# IO2.net
KiCad netlist of a schematic drawn in Altium Designer
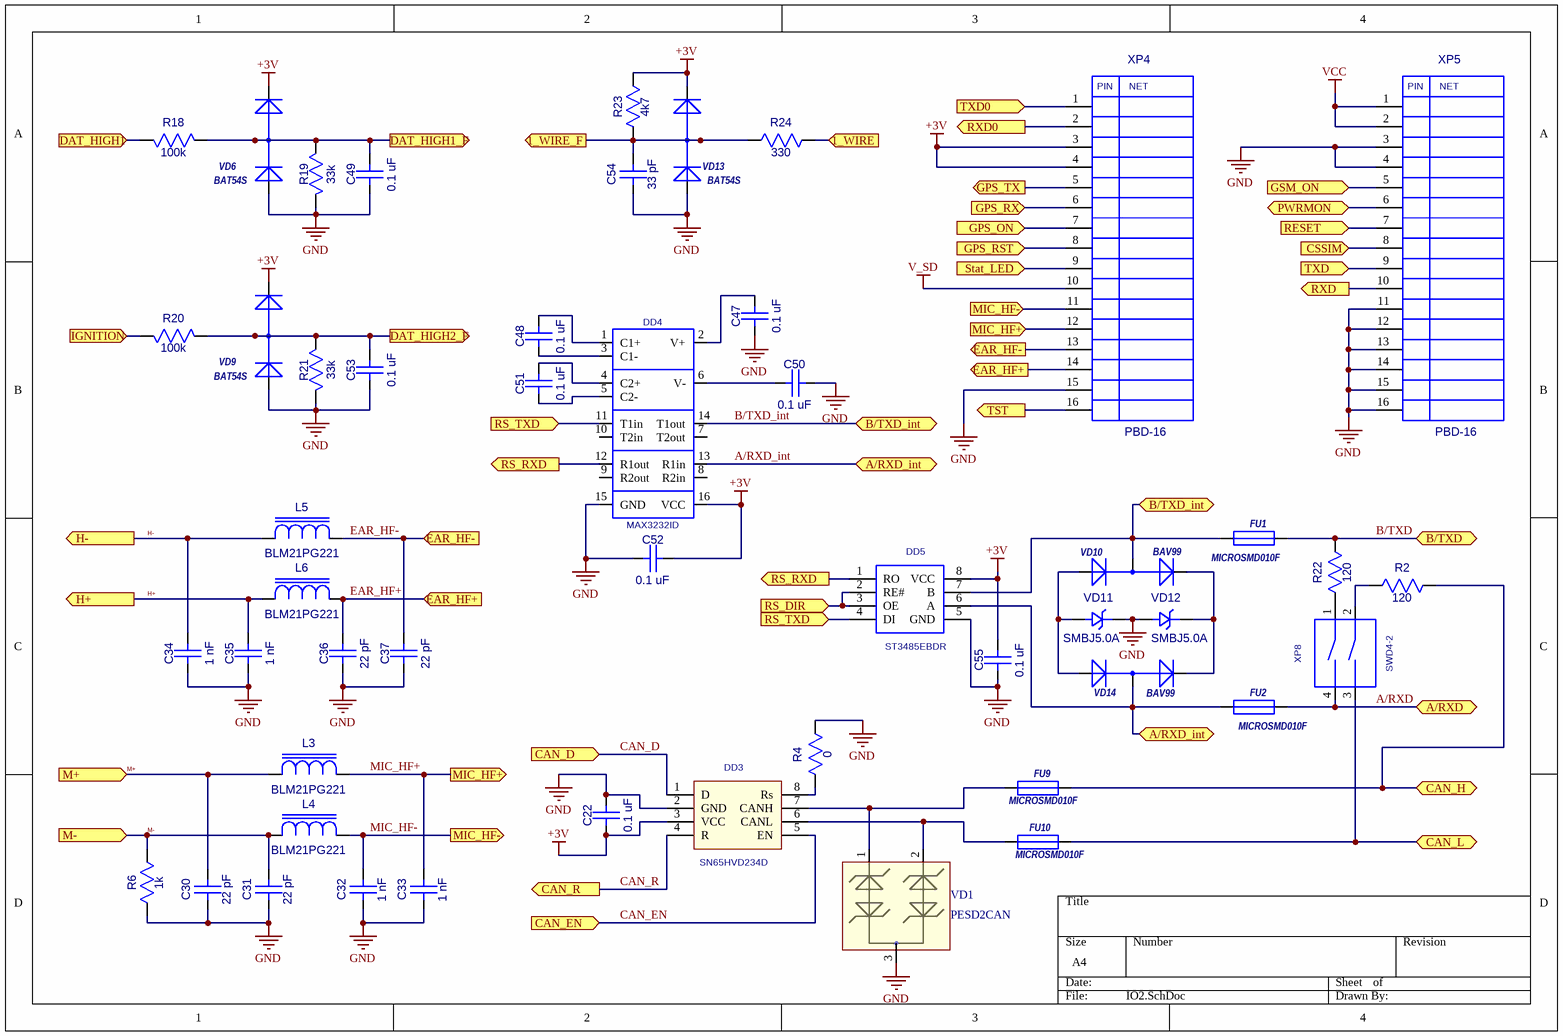
[diagram p0: IO2.SchDoc]

(export (version "E")
  (design (tool "Eeschema 10.0.6"))
  (components
    (comp (ref "C22")
      (value "0.1 uF")
      (footprint "CC0603-3M")
      (description "CC0603")
      (libsource (lib "*") (part "CC0603"))
    )
    (comp (ref "C30")
      (value "22 pF")
      (footprint "CC0603-3M")
      (description "CC0603")
      (libsource (lib "*") (part "CC0603"))
    )
    (comp (ref "C31")
      (value "22 pF")
      (footprint "CC0603-3M")
      (description "CC0603")
      (libsource (lib "*") (part "CC0603"))
    )
    (comp (ref "C32")
      (value "1 nF")
      (footprint "CC0603-3M")
      (description "CC0603")
      (libsource (lib "*") (part "CC0603"))
    )
    (comp (ref "C33")
      (value "1 nF")
      (footprint "CC0603-3M")
      (description "CC0603")
      (libsource (lib "*") (part "CC0603"))
    )
    (comp (ref "C34")
      (value "1 nF")
      (footprint "CC0603-3M")
      (description "CC0603")
      (libsource (lib "*") (part "CC0603"))
    )
    (comp (ref "C35")
      (value "1 nF")
      (footprint "CC0603-3M")
      (description "CC0603")
      (libsource (lib "*") (part "CC0603"))
    )
    (comp (ref "C36")
      (value "22 pF")
      (footprint "CC0603-3M")
      (description "CC0603")
      (libsource (lib "*") (part "CC0603"))
    )
    (comp (ref "C37")
      (value "22 pF")
      (footprint "CC0603-3M")
      (description "CC0603")
      (libsource (lib "*") (part "CC0603"))
    )
    (comp (ref "C47")
      (value "0.1 uF")
      (footprint "CC0603-3M")
      (description "CC0603")
      (libsource (lib "*") (part "CC0603"))
    )
    (comp (ref "C48")
      (value "0.1 uF")
      (footprint "CC0603-3M")
      (description "CC0603")
      (libsource (lib "*") (part "CC0603"))
    )
    (comp (ref "C49")
      (value "0.1 uF")
      (footprint "CC0603-3M")
      (description "CC0603")
      (libsource (lib "*") (part "CC0603"))
    )
    (comp (ref "C50")
      (value "0.1 uF")
      (footprint "CC0603-3M")
      (description "CC0603")
      (libsource (lib "*") (part "CC0603"))
    )
    (comp (ref "C51")
      (value "0.1 uF")
      (footprint "CC0603-3M")
      (description "CC0603")
      (libsource (lib "*") (part "CC0603"))
    )
    (comp (ref "C52")
      (value "0.1 uF")
      (footprint "CC0603-3M")
      (description "CC0603")
      (libsource (lib "*") (part "CC0603"))
    )
    (comp (ref "C53")
      (value "0.1 uF")
      (footprint "CC0603-3M")
      (description "CC0603")
      (libsource (lib "*") (part "CC0603"))
    )
    (comp (ref "C54")
      (value "33 pF")
      (footprint "CC0603-3M")
      (description "CC0603")
      (libsource (lib "*") (part "CC0603"))
    )
    (comp (ref "C55")
      (value "0.1 uF")
      (footprint "CC0603-3M")
      (description "CC0603")
      (libsource (lib "*") (part "CC0603"))
    )
    (comp (ref "DD3")
      (value "SN65HVD234D")
      (footprint "SO-8")
      (description "CAN Transceiver")
      (libsource (lib "gprs_modem") (part "SN65HVD234D"))
    )
    (comp (ref "DD4")
      (value "MAX3232ID")
      (footprint "SO16_M")
      (description "ST232BD/CD")
      (libsource (lib "Schetchik") (part "ST232BD/CD"))
    )
    (comp (ref "DD5")
      (value "ST3485EBDR")
      (footprint "SO-8")
      (description "SP485")
      (libsource (lib "Schetchik") (part "SP485"))
    )
    (comp (ref "FU1")
      (value "MICROSMD010F")
      (footprint "RC1210")
      (description "MICROSMD")
      (libsource (lib "*") (part "MICROSMD"))
    )
    (comp (ref "FU2")
      (value "MICROSMD010F")
      (footprint "RC1210")
      (description "MICROSMD")
      (libsource (lib "*") (part "MICROSMD"))
    )
    (comp (ref "FU9")
      (value "MICROSMD010F")
      (footprint "RC1210")
      (description "MICROSMD")
      (libsource (lib "*") (part "MICROSMD"))
    )
    (comp (ref "FU10")
      (value "MICROSMD010F")
      (footprint "RC1210")
      (description "MICROSMD")
      (libsource (lib "*") (part "MICROSMD"))
    )
    (comp (ref "L3")
      (value "BLM21PG221")
      (footprint "RC0805-MIDI-2")
      (libsource (lib "") (part "BLM21PG221_1"))
    )
    (comp (ref "L4")
      (value "BLM21PG221")
      (footprint "RC0805-MIDI-2")
      (libsource (lib "") (part "BLM21PG221_1"))
    )
    (comp (ref "L5")
      (value "BLM21PG221")
      (footprint "RC0805-MIDI-2")
      (libsource (lib "*") (part "BLM21PG221"))
    )
    (comp (ref "L6")
      (value "BLM21PG221")
      (footprint "RC0805-MIDI-2")
      (libsource (lib "*") (part "BLM21PG221"))
    )
    (comp (ref "R2")
      (value "120")
      (footprint "RC0805_IPC_NOM")
      (description "RC0805")
      (libsource (lib "gprs_modem") (part "RC0805"))
    )
    (comp (ref "R4")
      (value "0")
      (footprint "RC0603-3M")
      (description "RC0603")
      (libsource (lib "*") (part "RC0603"))
    )
    (comp (ref "R6")
      (value "1k")
      (footprint "RC0603-3M")
      (description "RC0603")
      (libsource (lib "*") (part "RC0603"))
    )
    (comp (ref "R18")
      (value "100k")
      (footprint "RC0603-3M")
      (description "RC0603")
      (libsource (lib "*") (part "RC0603"))
    )
    (comp (ref "R19")
      (value "33k")
      (footprint "RC0603-3M")
      (description "RC0603")
      (libsource (lib "*") (part "RC0603"))
    )
    (comp (ref "R20")
      (value "100k")
      (footprint "RC0603-3M")
      (description "RC0603")
      (libsource (lib "*") (part "RC0603"))
    )
    (comp (ref "R21")
      (value "33k")
      (footprint "RC0603-3M")
      (description "RC0603")
      (libsource (lib "*") (part "RC0603"))
    )
    (comp (ref "R22")
      (value "120")
      (footprint "RC0805_IPC_NOM")
      (description "RC0805")
      (libsource (lib "gprs_modem") (part "RC0805"))
    )
    (comp (ref "R23")
      (value "4k7")
      (footprint "RC0603-3M")
      (description "RC0603")
      (libsource (lib "*") (part "RC0603"))
    )
    (comp (ref "R24")
      (value "330")
      (footprint "RC0603-3M")
      (description "RC0603")
      (libsource (lib "*") (part "RC0603"))
    )
    (comp (ref "VD1")
      (value "PESD2CAN")
      (footprint "SOT-23(123)")
      (description "TVS for CAN")
      (libsource (lib "gprs_modem") (part "PESD2CAN"))
    )
    (comp (ref "VD6") (value "BAT54S") (footprint "SOT-23(GSD)") (libsource (lib "*") (part "BAT54S")))
    (comp (ref "VD9") (value "BAT54S") (footprint "SOT-23(GSD)") (libsource (lib "*") (part "BAT54S")))
    (comp (ref "VD10")
      (value "BAV99")
      (footprint "SOT-23(GSD)")
      (description "1.0 Ampere General Purpose Rectifier")
      (libsource (lib "gprs_modem") (part "BAV99"))
    )
    (comp (ref "VD11")
      (value "SMBJ5.0A")
      (footprint "SMB")
      (description "SMBJ")
      (libsource (lib "gprs_modem") (part "SMBJ"))
    )
    (comp (ref "VD12")
      (value "SMBJ5.0A")
      (footprint "SMB")
      (description "SMBJ")
      (libsource (lib "gprs_modem") (part "SMBJ"))
    )
    (comp (ref "VD13")
      (value "BAT54S")
      (footprint "SOT-23(GSD)")
      (description "1.0 Ampere General Purpose Rectifier")
      (libsource (lib "gprs_modem") (part "BAT54S"))
    )
    (comp (ref "VD14")
      (value "BAV99")
      (footprint "SOT-23(GSD)")
      (description "1.0 Ampere General Purpose Rectifier")
      (libsource (lib "gprs_modem") (part "BAV99"))
    )
    (comp (ref "XP4") (value "PBD-16") (footprint "PBD16") (libsource (lib "gprs_modem") (part "PBD-16")))
    (comp (ref "XP5") (value "PBD-16") (footprint "PBD16") (libsource (lib "gprs_modem") (part "PBD-16")))
    (comp (ref "XP8") (value "SWD4-2") (footprint "SWD4-2") (libsource (lib "gprs_modem") (part "SWD4-2")))
  )
  (nets
    (net (code "1") (name "+3V") (class "Default")
      (node (ref "C22") (pin "1") (pinfunction "A_1") (pintype "passive"))
      (node (ref "C52") (pin "2") (pinfunction "B_2") (pintype "passive"))
      (node (ref "C55") (pin "2") (pinfunction "B_2") (pintype "passive"))
      (node (ref "DD3") (pin "3") (pinfunction "VCC_3") (pintype "passive"))
      (node (ref "DD4") (pin "16") (pinfunction "VCC_16") (pintype "passive"))
      (node (ref "DD5") (pin "8") (pinfunction "VCC_8") (pintype "passive"))
      (node (ref "R23") (pin "1") (pinfunction "A_1") (pintype "passive"))
      (node (ref "VD13") (pin "2") (pinfunction "K_2") (pintype "passive"))
      (node (ref "VD6") (pin "2") (pinfunction "K_2") (pintype "passive"))
      (node (ref "VD9") (pin "2") (pinfunction "K_2") (pintype "passive"))
      (node (ref "XP4") (pin "3") (pinfunction "3_3") (pintype "passive"))
      (node (ref "XP4") (pin "4") (pinfunction "4_4") (pintype "passive"))
    )
    (net (code "2") (name "/1_WIRE") (class "Default")
      (node (ref "R24") (pin "2") (pinfunction "B_2") (pintype "passive"))
    )
    (net (code "3") (name "/1_WIRE_F") (class "Default")
      (node (ref "C54") (pin "2") (pinfunction "B_2") (pintype "passive"))
      (node (ref "R23") (pin "2") (pinfunction "B_2") (pintype "passive"))
      (node (ref "R24") (pin "1") (pinfunction "A_1") (pintype "passive"))
      (node (ref "VD13") (pin "3") (pinfunction "AK_3") (pintype "passive"))
    )
    (net (code "4") (name "/A{slash}RXD") (class "Default")
      (node (ref "FU2") (pin "1") (pintype "passive"))
      (node (ref "XP8") (pin "4") (pintype "passive"))
    )
    (net (code "5") (name "/A{slash}RXD_int") (class "Default")
      (node (ref "DD4") (pin "13") (pinfunction "R1in_13") (pintype "passive"))
      (node (ref "DD5") (pin "6") (pinfunction "A_6") (pintype "passive"))
      (node (ref "FU2") (pin "2") (pintype "passive"))
      (node (ref "VD14") (pin "3") (pinfunction "AK_3") (pintype "passive"))
    )
    (net (code "6") (name "/B{slash}TXD") (class "Default")
      (node (ref "FU1") (pin "1") (pintype "passive"))
      (node (ref "R22") (pin "2") (pinfunction "B_2") (pintype "passive"))
    )
    (net (code "7") (name "/B{slash}TXD_int") (class "Default")
      (node (ref "DD4") (pin "14") (pinfunction "T1out_14") (pintype "passive"))
      (node (ref "DD5") (pin "7") (pinfunction "B_7") (pintype "passive"))
      (node (ref "FU1") (pin "2") (pintype "passive"))
      (node (ref "VD10") (pin "3") (pinfunction "AK_3") (pintype "passive"))
    )
    (net (code "8") (name "/CAN_D") (class "Default")
      (node (ref "DD3") (pin "1") (pinfunction "D_1") (pintype "passive"))
    )
    (net (code "9") (name "/CAN_EN") (class "Default")
      (node (ref "DD3") (pin "5") (pinfunction "EN_5") (pintype "passive"))
    )
    (net (code "10") (name "/CAN_H") (class "Default")
      (node (ref "FU9") (pin "1") (pintype "passive"))
      (node (ref "R2") (pin "2") (pinfunction "B_2") (pintype "passive"))
    )
    (net (code "11") (name "/CAN_L") (class "Default")
      (node (ref "FU10") (pin "1") (pintype "passive"))
      (node (ref "XP8") (pin "3") (pintype "passive"))
    )
    (net (code "12") (name "/CAN_R") (class "Default")
      (node (ref "DD3") (pin "4") (pinfunction "R_4") (pintype "passive"))
    )
    (net (code "13") (name "/CSSIM") (class "Default")
      (node (ref "XP5") (pin "8") (pinfunction "8_8") (pintype "passive"))
    )
    (net (code "14") (name "/DAT_HIGH1") (class "Default")
      (node (ref "R18") (pin "2") (pinfunction "B_2") (pintype "passive"))
    )
    (net (code "15") (name "/DAT_HIGH1_F") (class "Default")
      (node (ref "C49") (pin "2") (pinfunction "B_2") (pintype "passive"))
      (node (ref "R18") (pin "1") (pinfunction "A_1") (pintype "passive"))
      (node (ref "R19") (pin "1") (pinfunction "A_1") (pintype "passive"))
      (node (ref "VD6") (pin "3") (pinfunction "AK_3") (pintype "passive"))
    )
    (net (code "16") (name "/DAT_HIGH2_F") (class "Default")
      (node (ref "C53") (pin "2") (pinfunction "B_2") (pintype "passive"))
      (node (ref "R20") (pin "1") (pinfunction "A_1") (pintype "passive"))
      (node (ref "R21") (pin "1") (pinfunction "A_1") (pintype "passive"))
      (node (ref "VD9") (pin "3") (pinfunction "AK_3") (pintype "passive"))
    )
    (net (code "17") (name "/EAR_HF+") (class "Default")
      (node (ref "C36") (pin "2") (pinfunction "B_2") (pintype "passive"))
      (node (ref "L6") (pin "1") (pinfunction "A_1") (pintype "passive"))
      (node (ref "XP4") (pin "14") (pinfunction "14_14") (pintype "passive"))
    )
    (net (code "18") (name "/EAR_HF-") (class "Default")
      (node (ref "C37") (pin "2") (pinfunction "B_2") (pintype "passive"))
      (node (ref "L5") (pin "1") (pinfunction "A_1") (pintype "passive"))
      (node (ref "XP4") (pin "13") (pinfunction "13_13") (pintype "passive"))
    )
    (net (code "19") (name "/GPS_ON") (class "Default")
      (node (ref "XP4") (pin "7") (pinfunction "7_7") (pintype "passive"))
    )
    (net (code "20") (name "/GPS_RST") (class "Default")
      (node (ref "XP4") (pin "8") (pinfunction "8_8") (pintype "passive"))
    )
    (net (code "21") (name "/GPS_RX") (class "Default")
      (node (ref "XP4") (pin "6") (pinfunction "6_6") (pintype "passive"))
    )
    (net (code "22") (name "/GPS_TX") (class "Default")
      (node (ref "XP4") (pin "5") (pinfunction "5_5") (pintype "passive"))
    )
    (net (code "23") (name "/GSM_ON") (class "Default")
      (node (ref "XP5") (pin "5") (pinfunction "5_5") (pintype "passive"))
    )
    (net (code "24") (name "/H+") (class "Default")
      (node (ref "C35") (pin "2") (pinfunction "B_2") (pintype "passive"))
      (node (ref "L6") (pin "2") (pinfunction "B_2") (pintype "passive"))
    )
    (net (code "25") (name "/H-") (class "Default")
      (node (ref "C34") (pin "2") (pinfunction "B_2") (pintype "passive"))
      (node (ref "L5") (pin "2") (pinfunction "B_2") (pintype "passive"))
    )
    (net (code "26") (name "/IGNITION") (class "Default")
      (node (ref "R20") (pin "2") (pinfunction "B_2") (pintype "passive"))
    )
    (net (code "27") (name "/M+") (class "Default")
      (node (ref "C30") (pin "2") (pinfunction "B_2") (pintype "passive"))
      (node (ref "L3") (pin "1") (pinfunction "A_1") (pintype "passive"))
    )
    (net (code "28") (name "/M-") (class "Default")
      (node (ref "C31") (pin "2") (pinfunction "B_2") (pintype "passive"))
      (node (ref "L4") (pin "1") (pinfunction "A_1") (pintype "passive"))
      (node (ref "R6") (pin "2") (pinfunction "B_2") (pintype "passive"))
    )
    (net (code "29") (name "/MIC_HF+") (class "Default")
      (node (ref "C33") (pin "2") (pinfunction "B_2") (pintype "passive"))
      (node (ref "L3") (pin "2") (pinfunction "B_2") (pintype "passive"))
      (node (ref "XP4") (pin "12") (pinfunction "12_12") (pintype "passive"))
    )
    (net (code "30") (name "/MIC_HF-") (class "Default")
      (node (ref "C32") (pin "2") (pinfunction "B_2") (pintype "passive"))
      (node (ref "L4") (pin "2") (pinfunction "B_2") (pintype "passive"))
      (node (ref "XP4") (pin "11") (pinfunction "11_11") (pintype "passive"))
    )
    (net (code "31") (name "/PWRMON") (class "Default")
      (node (ref "XP5") (pin "6") (pinfunction "6_6") (pintype "passive"))
    )
    (net (code "32") (name "/RESET") (class "Default")
      (node (ref "XP5") (pin "7") (pinfunction "7_7") (pintype "passive"))
    )
    (net (code "33") (name "/RS_DIR") (class "Default")
      (node (ref "DD5") (pin "2") (pinfunction "RE#_2") (pintype "passive"))
      (node (ref "DD5") (pin "3") (pinfunction "OE_3") (pintype "passive"))
    )
    (net (code "34") (name "/RS_RXD") (class "Default")
      (node (ref "DD4") (pin "12") (pinfunction "R1out_12") (pintype "passive"))
      (node (ref "DD5") (pin "1") (pinfunction "RO_1") (pintype "passive"))
    )
    (net (code "35") (name "/RS_TXD") (class "Default")
      (node (ref "DD4") (pin "11") (pinfunction "T1in_11") (pintype "passive"))
      (node (ref "DD5") (pin "4") (pinfunction "DI_4") (pintype "passive"))
    )
    (net (code "36") (name "/RXD") (class "Default")
      (node (ref "XP5") (pin "10") (pinfunction "10_10") (pintype "passive"))
    )
    (net (code "37") (name "/RXD0") (class "Default")
      (node (ref "XP4") (pin "2") (pinfunction "2_2") (pintype "passive"))
    )
    (net (code "38") (name "/Stat_LED") (class "Default")
      (node (ref "XP4") (pin "9") (pinfunction "9_9") (pintype "passive"))
    )
    (net (code "39") (name "/TST") (class "Default")
      (node (ref "XP4") (pin "16") (pinfunction "16_16") (pintype "passive"))
    )
    (net (code "40") (name "/TXD") (class "Default")
      (node (ref "XP5") (pin "9") (pinfunction "9_9") (pintype "passive"))
    )
    (net (code "41") (name "/TXD0") (class "Default")
      (node (ref "XP4") (pin "1") (pinfunction "1_1") (pintype "passive"))
    )
    (net (code "42") (name "GND") (class "Default")
      (node (ref "C22") (pin "2") (pinfunction "B_2") (pintype "passive"))
      (node (ref "C30") (pin "1") (pinfunction "A_1") (pintype "passive"))
      (node (ref "C31") (pin "1") (pinfunction "A_1") (pintype "passive"))
      (node (ref "C32") (pin "1") (pinfunction "A_1") (pintype "passive"))
      (node (ref "C33") (pin "1") (pinfunction "A_1") (pintype "passive"))
      (node (ref "C34") (pin "1") (pinfunction "A_1") (pintype "passive"))
      (node (ref "C35") (pin "1") (pinfunction "A_1") (pintype "passive"))
      (node (ref "C36") (pin "1") (pinfunction "A_1") (pintype "passive"))
      (node (ref "C37") (pin "1") (pinfunction "A_1") (pintype "passive"))
      (node (ref "C47") (pin "1") (pinfunction "A_1") (pintype "passive"))
      (node (ref "C49") (pin "1") (pinfunction "A_1") (pintype "passive"))
      (node (ref "C50") (pin "1") (pinfunction "A_1") (pintype "passive"))
      (node (ref "C52") (pin "1") (pinfunction "A_1") (pintype "passive"))
      (node (ref "C53") (pin "1") (pinfunction "A_1") (pintype "passive"))
      (node (ref "C54") (pin "1") (pinfunction "A_1") (pintype "passive"))
      (node (ref "C55") (pin "1") (pinfunction "A_1") (pintype "passive"))
      (node (ref "DD3") (pin "2") (pinfunction "GND_2") (pintype "passive"))
      (node (ref "DD4") (pin "15") (pinfunction "GND_15") (pintype "passive"))
      (node (ref "DD5") (pin "5") (pinfunction "GND_5") (pintype "passive"))
      (node (ref "R19") (pin "2") (pinfunction "B_2") (pintype "passive"))
      (node (ref "R21") (pin "2") (pinfunction "B_2") (pintype "passive"))
      (node (ref "R4") (pin "2") (pinfunction "B_2") (pintype "passive"))
      (node (ref "R6") (pin "1") (pinfunction "A_1") (pintype "passive"))
      (node (ref "VD1") (pin "3") (pinfunction "3_3") (pintype "passive"))
      (node (ref "VD11") (pin "2") (pinfunction "K_2") (pintype "passive"))
      (node (ref "VD12") (pin "1") (pinfunction "A_1") (pintype "passive"))
      (node (ref "VD13") (pin "1") (pinfunction "A_1") (pintype "passive"))
      (node (ref "VD6") (pin "1") (pinfunction "A_1") (pintype "passive"))
      (node (ref "VD9") (pin "1") (pinfunction "A_1") (pintype "passive"))
      (node (ref "XP4") (pin "15") (pinfunction "15_15") (pintype "passive"))
      (node (ref "XP5") (pin "11") (pinfunction "11_11") (pintype "passive"))
      (node (ref "XP5") (pin "12") (pinfunction "12_12") (pintype "passive"))
      (node (ref "XP5") (pin "13") (pinfunction "13_13") (pintype "passive"))
      (node (ref "XP5") (pin "14") (pinfunction "14_14") (pintype "passive"))
      (node (ref "XP5") (pin "15") (pinfunction "15_15") (pintype "passive"))
      (node (ref "XP5") (pin "16") (pinfunction "16_16") (pintype "passive"))
      (node (ref "XP5") (pin "3") (pinfunction "3_3") (pintype "passive"))
      (node (ref "XP5") (pin "4") (pinfunction "4_4") (pintype "passive"))
    )
    (net (code "43") (name "Net-(C47-B)") (class "Default")
      (node (ref "C47") (pin "2") (pinfunction "B_2") (pintype "passive"))
      (node (ref "DD4") (pin "2") (pinfunction "V+_2") (pintype "passive"))
    )
    (net (code "44") (name "Net-(C48-A)") (class "Default")
      (node (ref "C48") (pin "1") (pinfunction "A_1") (pintype "passive"))
      (node (ref "DD4") (pin "3") (pinfunction "C1-_3") (pintype "passive"))
    )
    (net (code "45") (name "Net-(C48-B)") (class "Default")
      (node (ref "C48") (pin "2") (pinfunction "B_2") (pintype "passive"))
      (node (ref "DD4") (pin "1") (pinfunction "C1+_1") (pintype "passive"))
    )
    (net (code "46") (name "Net-(C50-B)") (class "Default")
      (node (ref "C50") (pin "2") (pinfunction "B_2") (pintype "passive"))
      (node (ref "DD4") (pin "6") (pinfunction "V-_6") (pintype "passive"))
    )
    (net (code "47") (name "Net-(C51-A)") (class "Default")
      (node (ref "C51") (pin "1") (pinfunction "A_1") (pintype "passive"))
      (node (ref "DD4") (pin "5") (pinfunction "C2-_5") (pintype "passive"))
    )
    (net (code "48") (name "Net-(C51-B)") (class "Default")
      (node (ref "C51") (pin "2") (pinfunction "B_2") (pintype "passive"))
      (node (ref "DD4") (pin "4") (pinfunction "C2+_4") (pintype "passive"))
    )
    (net (code "49") (name "Net-(DD3-CANH)") (class "Default")
      (node (ref "DD3") (pin "7") (pinfunction "CANH_7") (pintype "passive"))
      (node (ref "FU9") (pin "2") (pintype "passive"))
      (node (ref "VD1") (pin "1") (pinfunction "1_1") (pintype "passive"))
    )
    (net (code "50") (name "Net-(DD3-CANL)") (class "Default")
      (node (ref "DD3") (pin "6") (pinfunction "CANL_6") (pintype "passive"))
      (node (ref "FU10") (pin "2") (pintype "passive"))
      (node (ref "VD1") (pin "2") (pinfunction "2_2") (pintype "passive"))
    )
    (net (code "51") (name "Net-(DD3-Rs)") (class "Default")
      (node (ref "DD3") (pin "8") (pinfunction "Rs_8") (pintype "passive"))
      (node (ref "R4") (pin "1") (pinfunction "A_1") (pintype "passive"))
    )
    (net (code "52") (name "Net-(R2-A)") (class "Default")
      (node (ref "R2") (pin "1") (pinfunction "A_1") (pintype "passive"))
      (node (ref "XP8") (pin "2") (pintype "passive"))
    )
    (net (code "53") (name "Net-(R22-A)") (class "Default")
      (node (ref "R22") (pin "1") (pinfunction "A_1") (pintype "passive"))
      (node (ref "XP8") (pin "1") (pintype "passive"))
    )
    (net (code "54") (name "Net-(VD10-A)") (class "Default")
      (node (ref "VD10") (pin "1") (pinfunction "A_1") (pintype "passive"))
      (node (ref "VD11") (pin "1") (pinfunction "A_1") (pintype "passive"))
      (node (ref "VD14") (pin "1") (pinfunction "A_1") (pintype "passive"))
    )
    (net (code "55") (name "Net-(VD10-K)") (class "Default")
      (node (ref "VD10") (pin "2") (pinfunction "K_2") (pintype "passive"))
      (node (ref "VD12") (pin "2") (pinfunction "K_2") (pintype "passive"))
      (node (ref "VD14") (pin "2") (pinfunction "K_2") (pintype "passive"))
    )
    (net (code "56") (name "VCC") (class "Default")
      (node (ref "XP5") (pin "1") (pinfunction "1_1") (pintype "passive"))
      (node (ref "XP5") (pin "2") (pinfunction "2_2") (pintype "passive"))
    )
    (net (code "57") (name "V_SD") (class "Default")
      (node (ref "XP4") (pin "10") (pinfunction "10_10") (pintype "passive"))
    )
    (net (code "58") (name "unconnected-(DD4-R2in-Pad8)") (class "Default")
      (node (ref "DD4") (pin "8") (pinfunction "R2in_8") (pintype "passive"))
    )
    (net (code "59") (name "unconnected-(DD4-R2out-Pad9)") (class "Default")
      (node (ref "DD4") (pin "9") (pinfunction "R2out_9") (pintype "passive"))
    )
    (net (code "60") (name "unconnected-(DD4-T2in-Pad10)") (class "Default")
      (node (ref "DD4") (pin "10") (pinfunction "T2in_10") (pintype "passive"))
    )
    (net (code "61") (name "unconnected-(DD4-T2out-Pad7)") (class "Default")
      (node (ref "DD4") (pin "7") (pinfunction "T2out_7") (pintype "passive"))
    )
  )
)
